# ControlBoardV3-4L.net
KiCad netlist of a schematic drawn in EAGLE
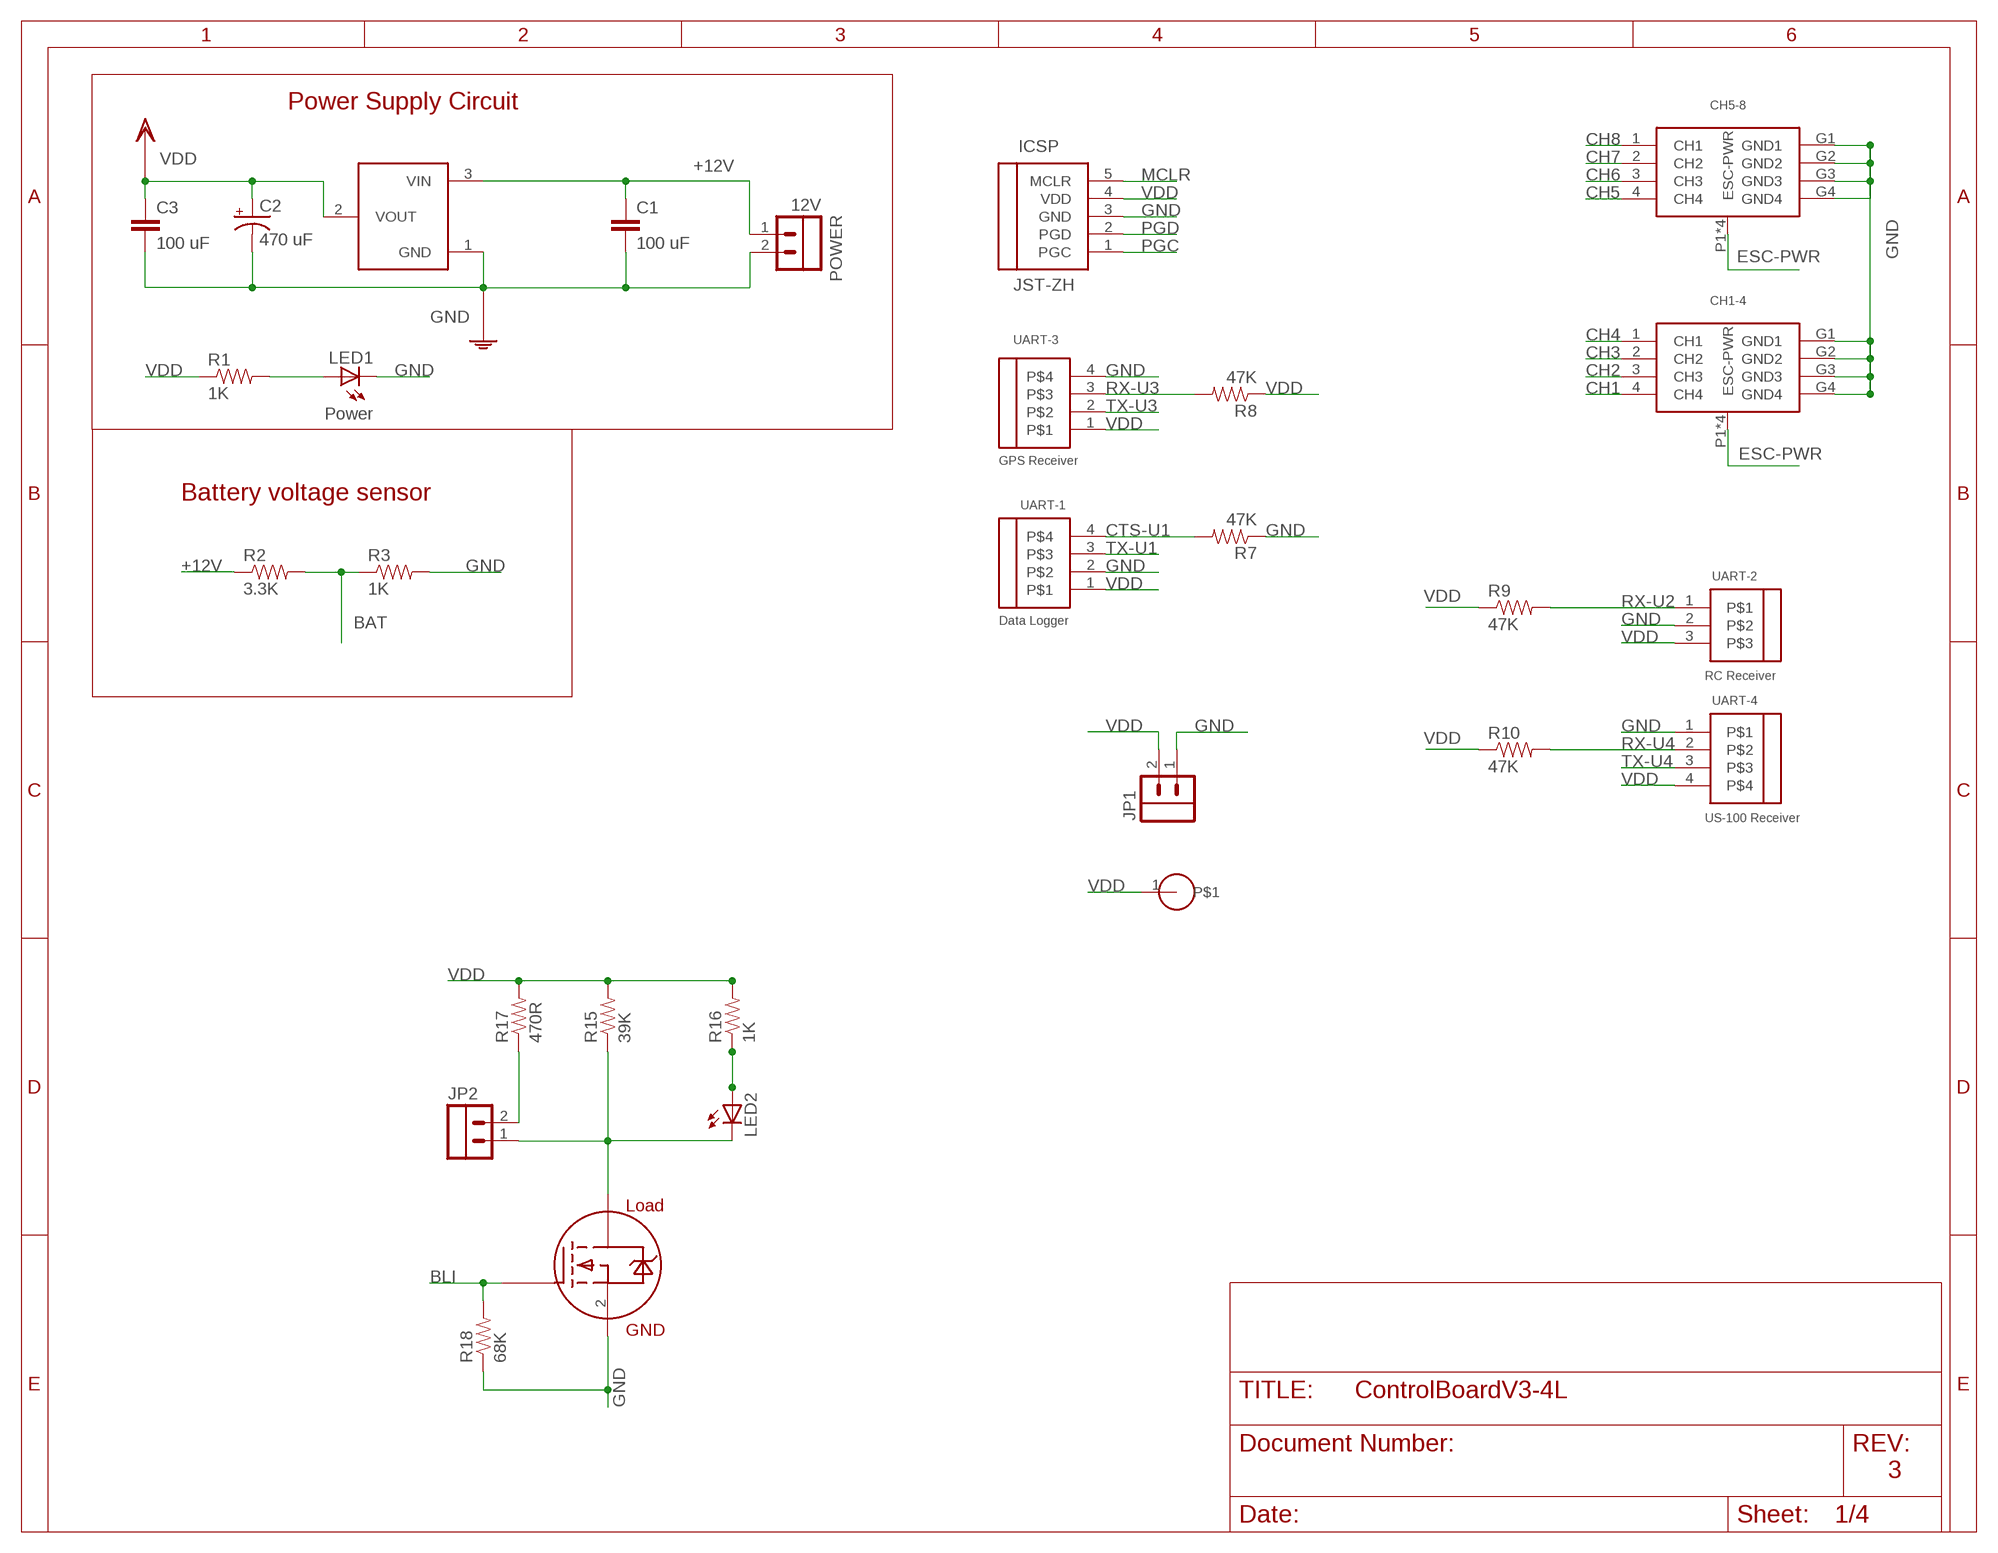
[diagram p0: schematic, sheet 1]
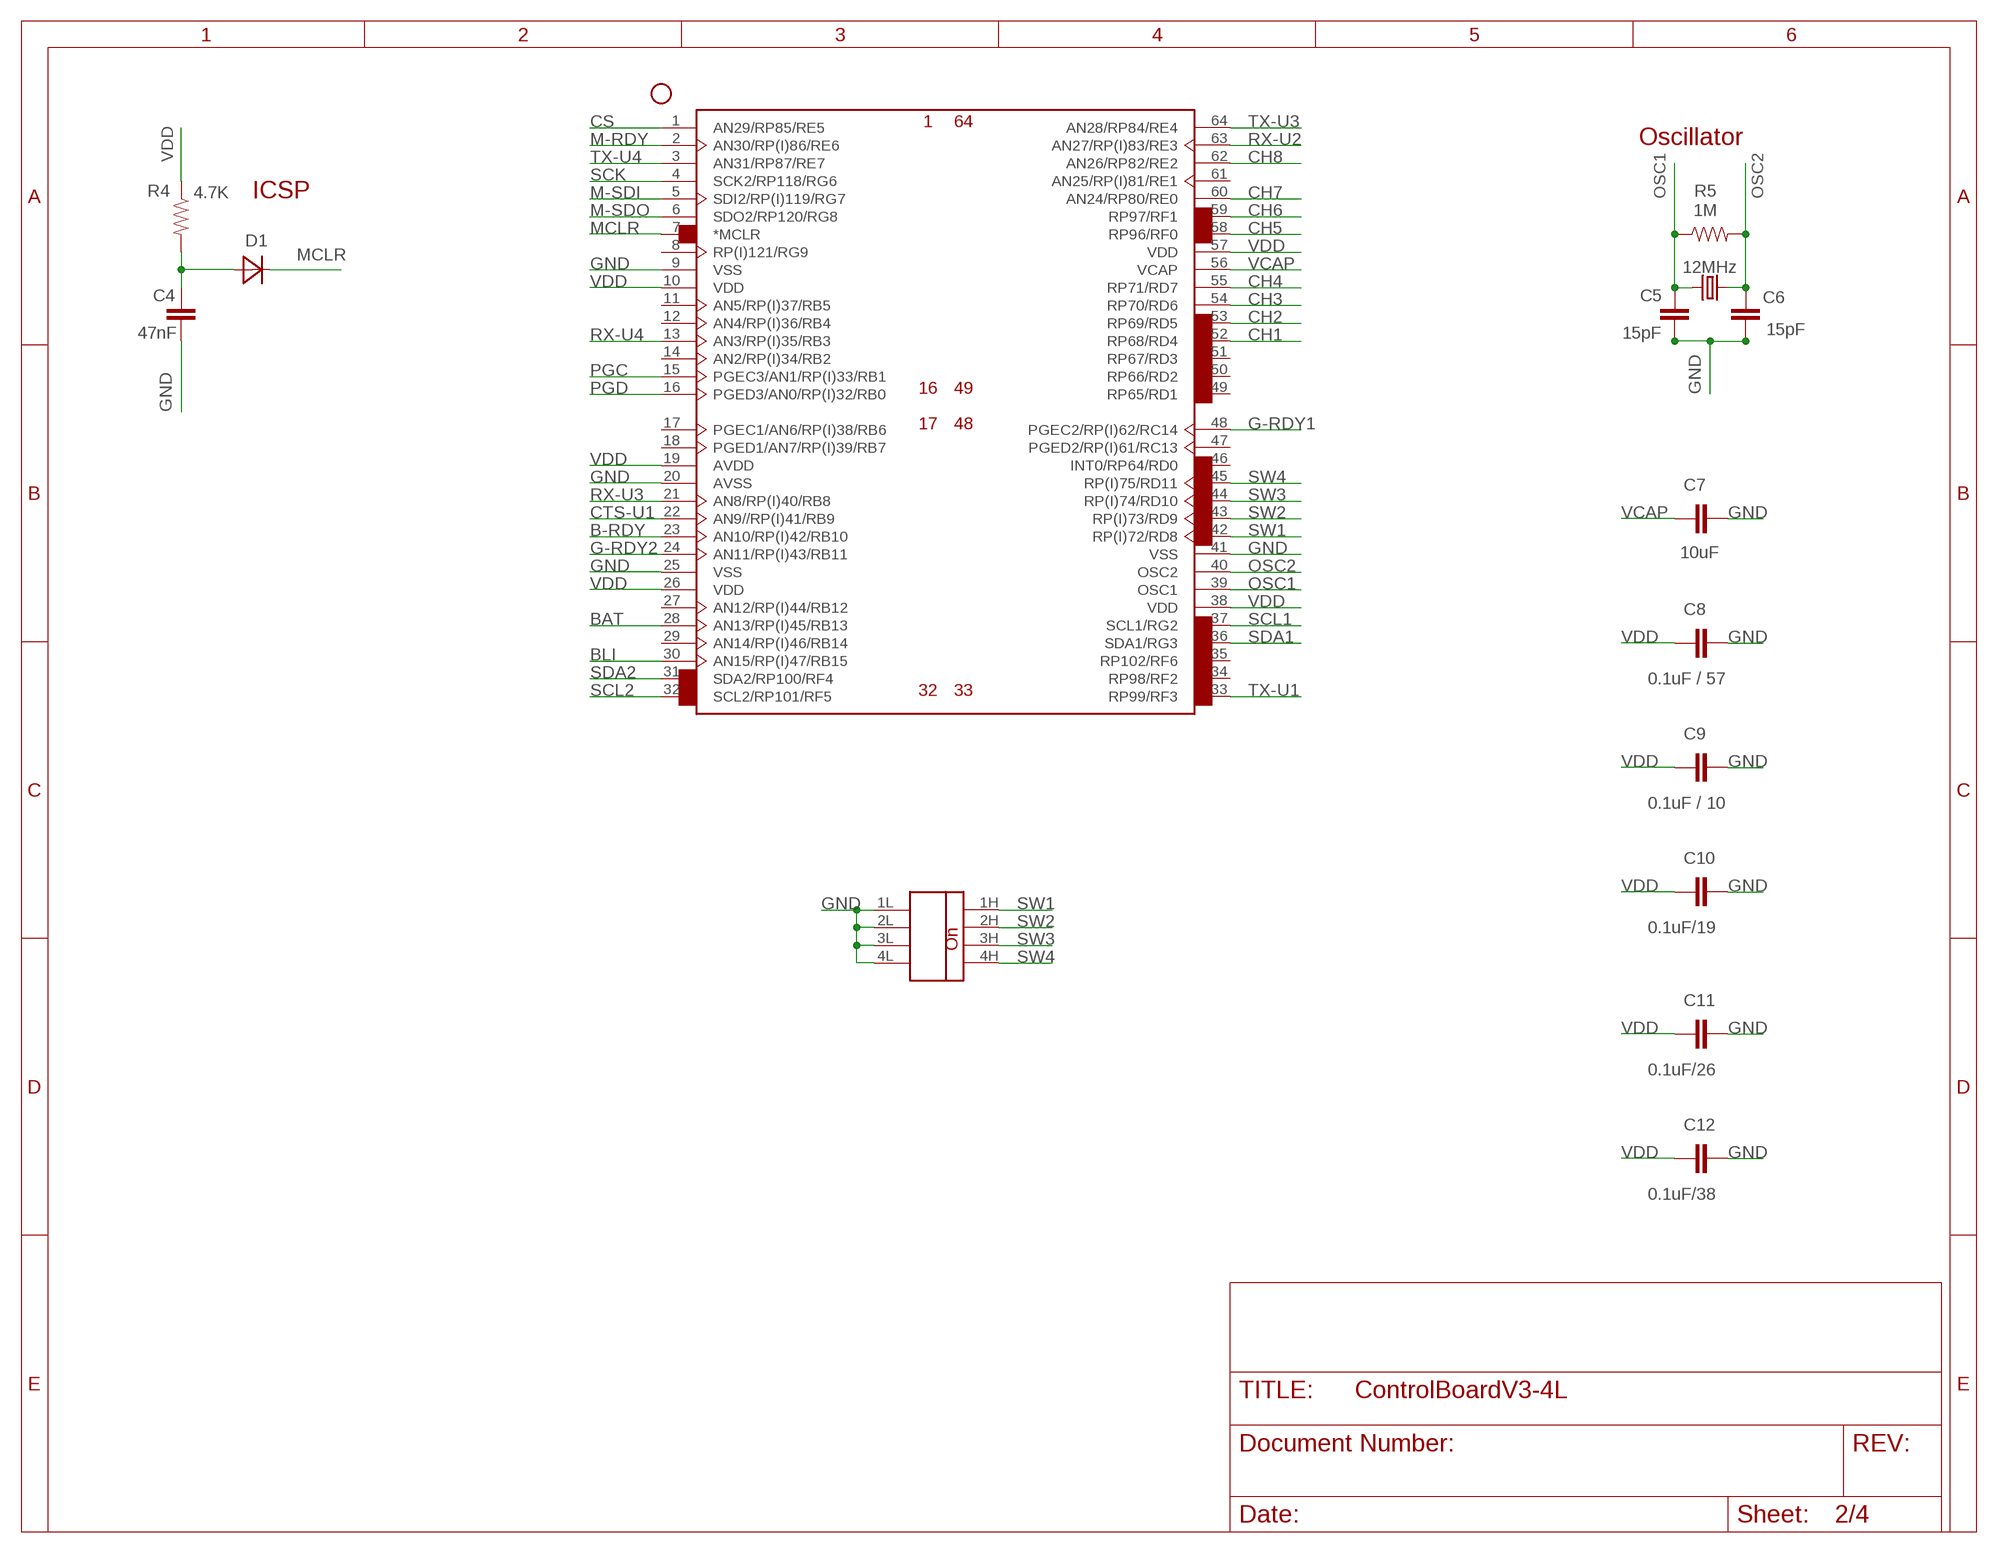
[diagram p1: schematic, sheet 2]
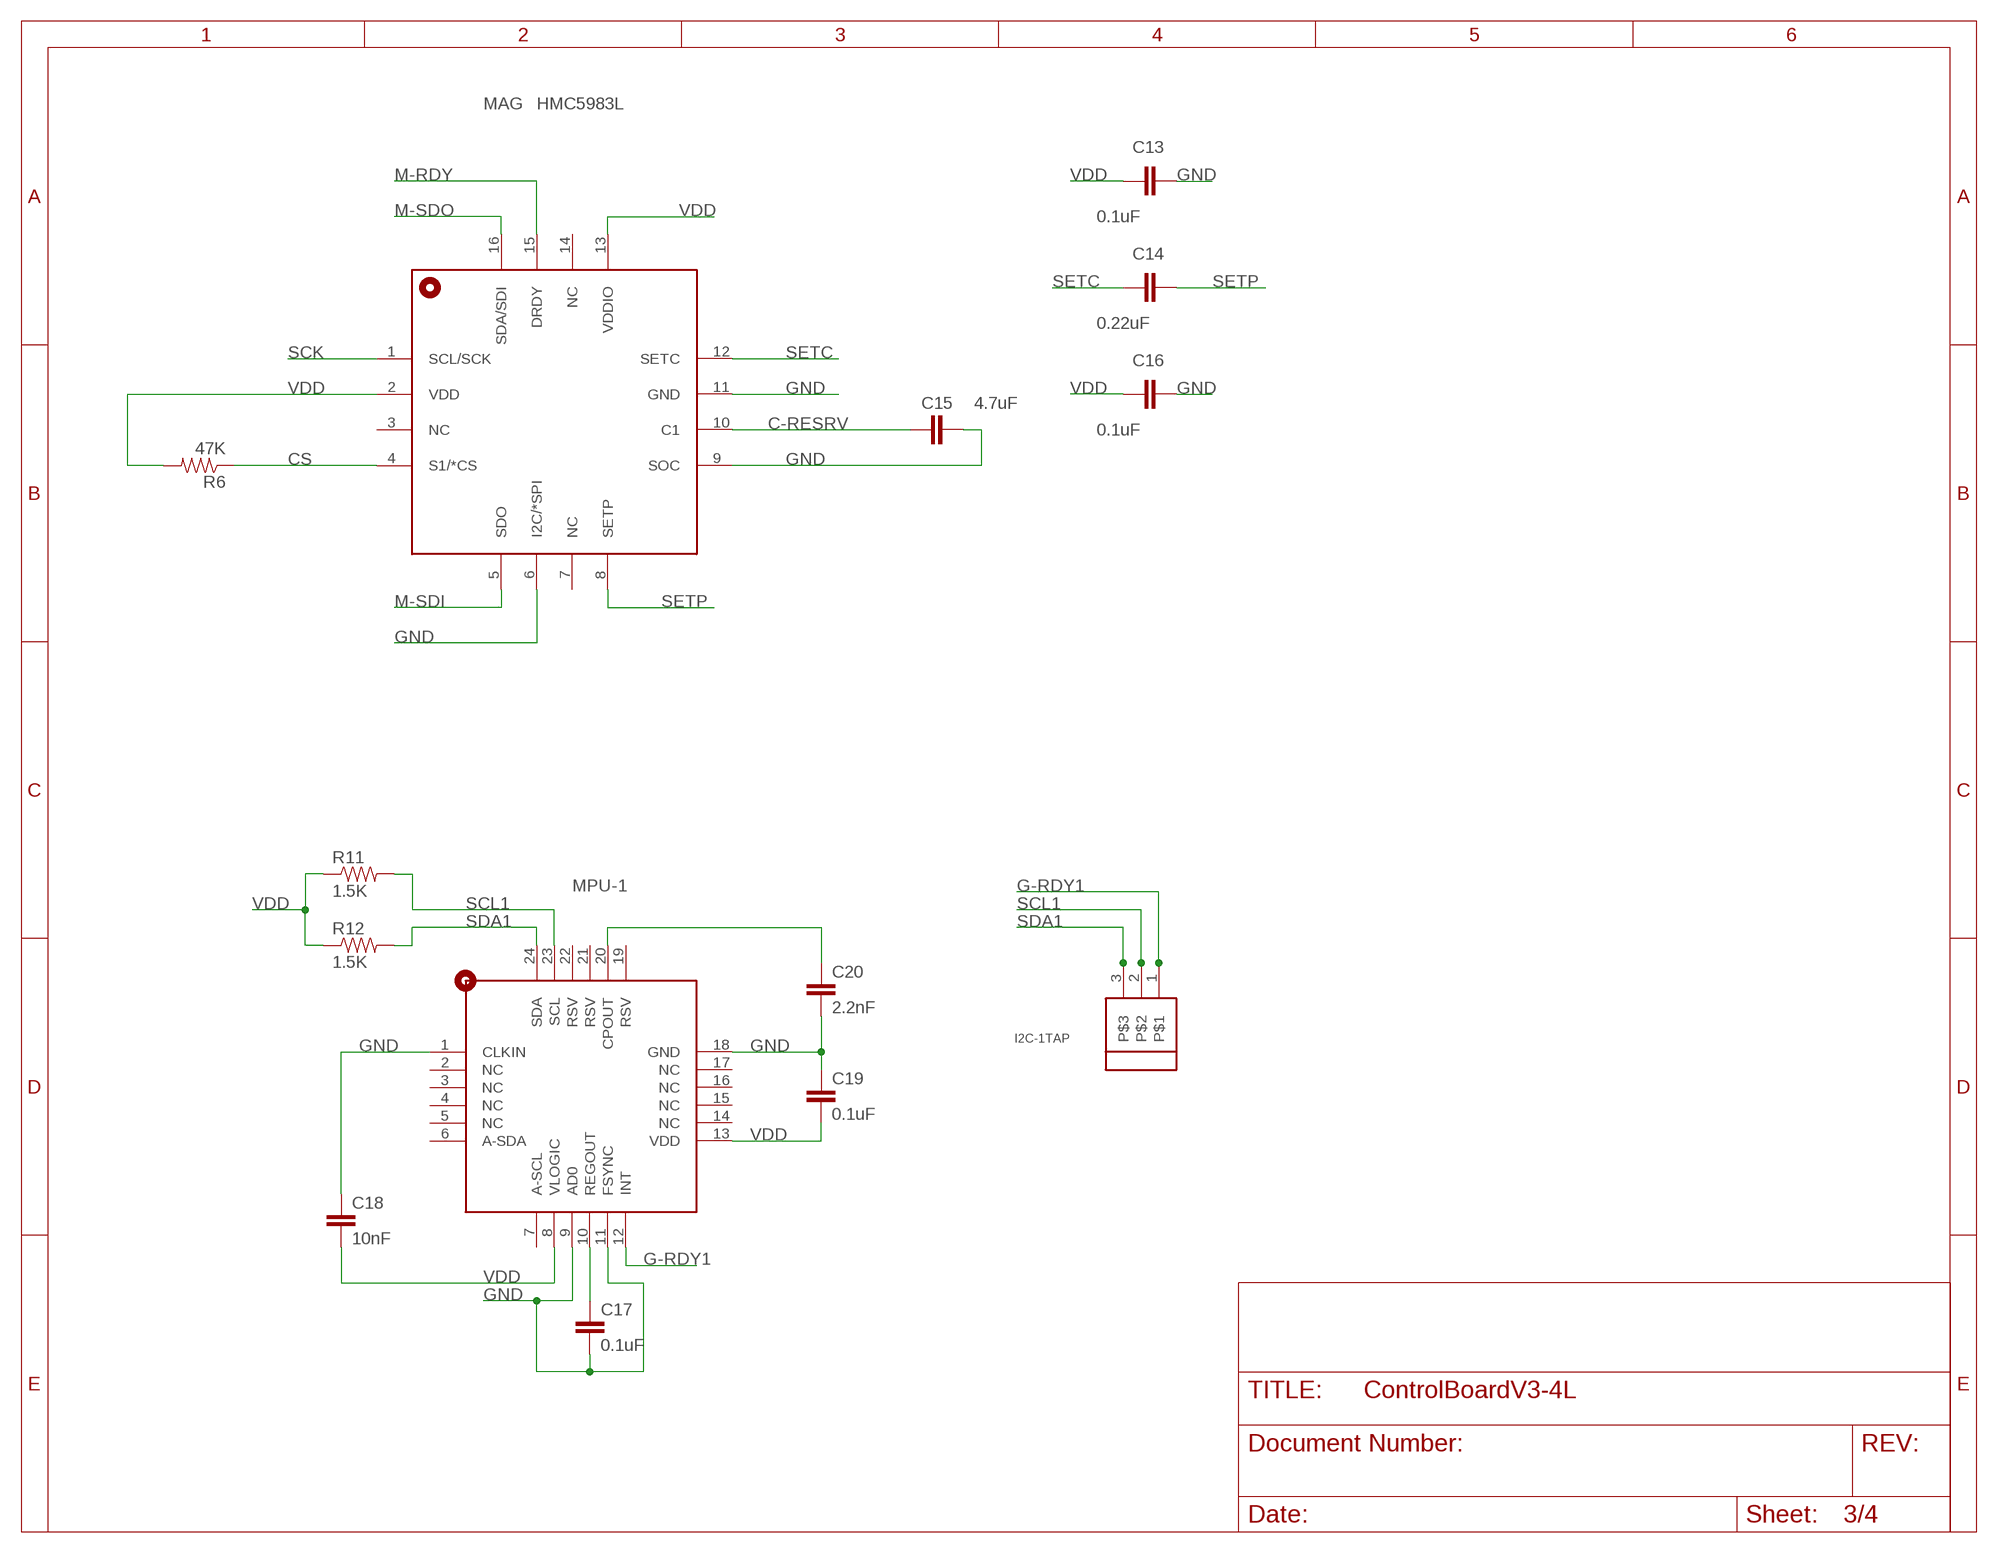
[diagram p2: schematic, sheet 3]
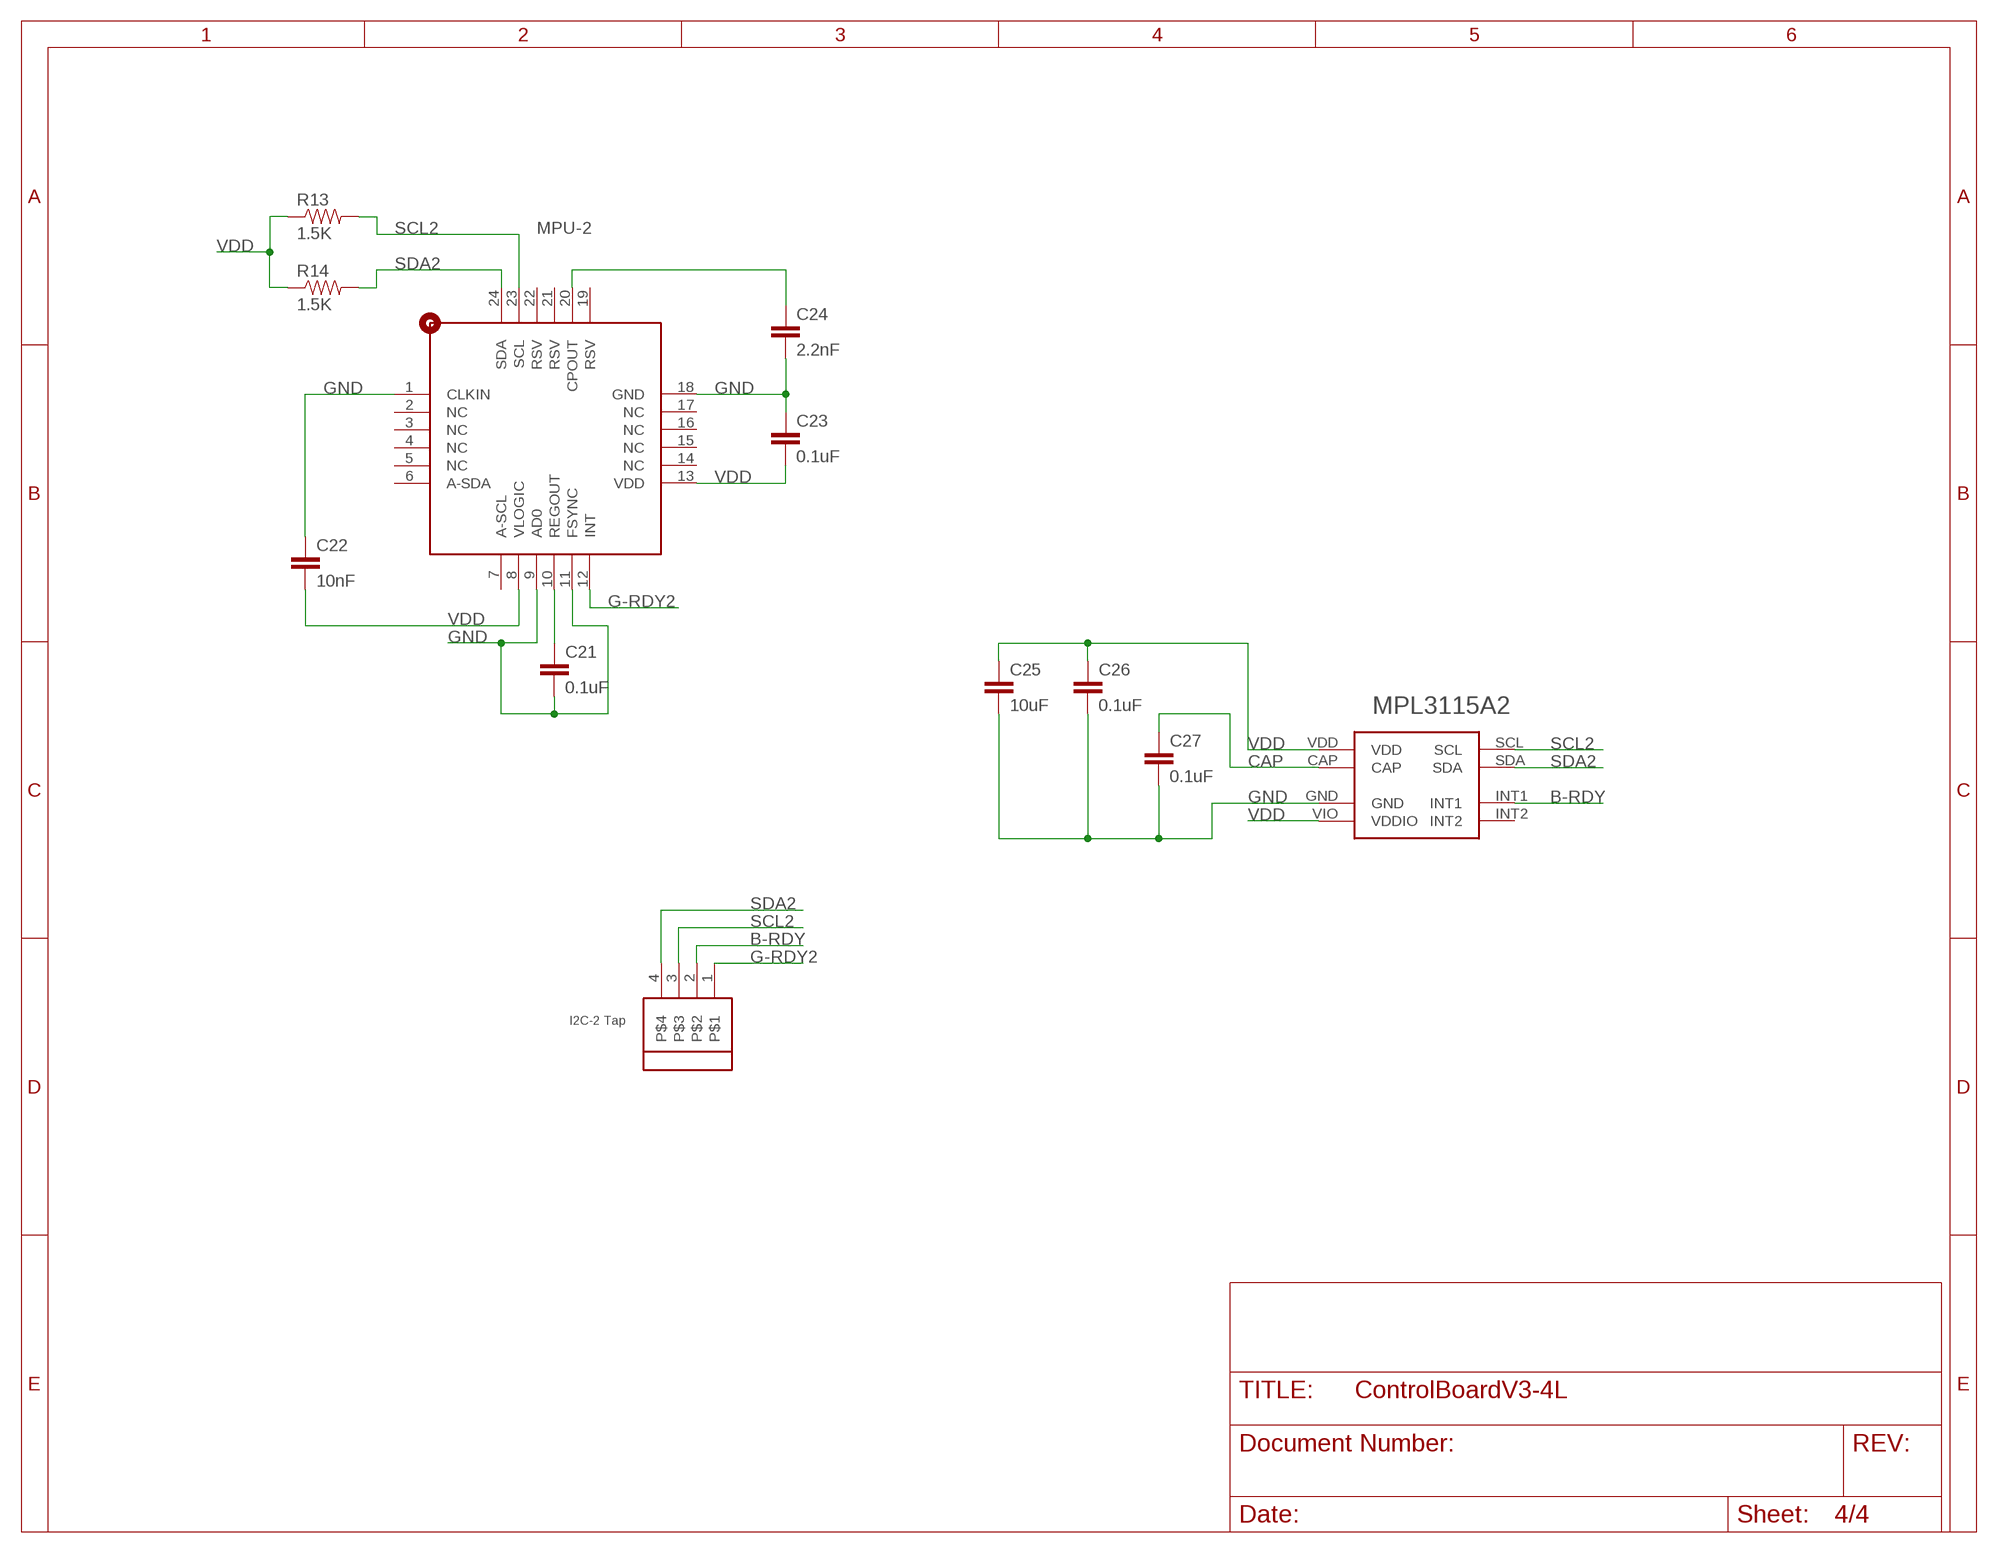
[diagram p3: schematic, sheet 4]

(export (version "E")
  (design (tool "Eeschema 10.0.6"))
  (components
    (comp (ref "C4")
      (value "47nF")
      (footprint "eagle-import:0805_INCH-HS-CAP")
      (libsource (lib "eagle-import") (part "CAP-CERAMIC_0805"))
    )
    (comp (ref "C5")
      (value "15pF")
      (footprint "eagle-import:0805_INCH-HS-CAP")
      (libsource (lib "eagle-import") (part "CAP-CERAMIC_0805"))
    )
    (comp (ref "C6")
      (value "15pF")
      (footprint "eagle-import:0805_INCH-HS-CAP")
      (libsource (lib "eagle-import") (part "CAP-CERAMIC_0805"))
    )
    (comp (ref "C7")
      (value "10uF")
      (footprint "eagle-import:1210_INCH-HS-CAP")
      (libsource (lib "eagle-import") (part "CAP-CERAMIC_1210"))
    )
    (comp (ref "C8")
      (value "0.1uF / 57")
      (footprint "eagle-import:0603_INCH-HS-CAP")
      (libsource (lib "eagle-import") (part "CAP-CERAMIC_0603"))
    )
    (comp (ref "C9")
      (value "0.1uF / 10")
      (footprint "eagle-import:0603_INCH-HS-CAP")
      (libsource (lib "eagle-import") (part "CAP-CERAMIC_0603"))
    )
    (comp (ref "C10")
      (value "0.1uF/19")
      (footprint "eagle-import:0603_INCH-HS-CAP")
      (libsource (lib "eagle-import") (part "CAP-CERAMIC_0603"))
    )
    (comp (ref "C11")
      (value "0.1uF/26")
      (footprint "eagle-import:0603_INCH-HS-CAP")
      (libsource (lib "eagle-import") (part "CAP-CERAMIC_0603"))
    )
    (comp (ref "C12")
      (value "0.1uF/38")
      (footprint "eagle-import:0603_INCH-HS-CAP")
      (libsource (lib "eagle-import") (part "CAP-CERAMIC_0603"))
    )
    (comp (ref "D1")
      (value "DIODE_1206")
      (footprint "eagle-import:1206_INCH-HS-DIODE")
      (libsource (lib "eagle-import") (part "DIODE_1206"))
    )
    (comp (ref "Q1")
      (value "12MHz")
      (footprint "eagle-import:CRYSTAL-SMD-5.0X3.2")
      (libsource (lib "eagle-import") (part "CRYSTAL_SMD-5.0X3.2"))
    )
    (comp (ref "R4")
      (value "4.7K")
      (footprint "eagle-import:0805_INCH-HS")
      (libsource (lib "eagle-import") (part "RESISTOR_0805"))
    )
    (comp (ref "R5")
      (value "1M")
      (footprint "eagle-import:0805_INCH-HS")
      (libsource (lib "eagle-import") (part "RESISTOR_0805"))
    )
    (comp (ref "U$1")
      (value "PIC24EP512GP806_TQFP64-10X10")
      (footprint "eagle-import:TQFP64-10X10X1MM")
      (libsource (lib "eagle-import") (part "PIC24EP512GP806_TQFP64-10X10"))
    )
    (comp (ref "U$3")
      (value "SWITCH-4_HALF-PITCH")
      (footprint "eagle-import:DIP-4-HP")
      (libsource (lib "eagle-import") (part "SWITCH-4_HALF-PITCH"))
    )
    (comp (ref "C21")
      (value "0.1uF")
      (footprint "eagle-import:0603_INCH-HS-CAP")
      (libsource (lib "eagle-import") (part "CAP-CERAMIC_0603"))
    )
    (comp (ref "C22")
      (value "10nF")
      (footprint "eagle-import:0603_INCH-HS-CAP")
      (libsource (lib "eagle-import") (part "CAP-CERAMIC_0603"))
    )
    (comp (ref "C23")
      (value "0.1uF")
      (footprint "eagle-import:0603_INCH-HS-CAP")
      (libsource (lib "eagle-import") (part "CAP-CERAMIC_0603"))
    )
    (comp (ref "C24")
      (value "2.2nF")
      (footprint "eagle-import:0805_INCH-HS-CAP")
      (libsource (lib "eagle-import") (part "CAP-CERAMIC_0805"))
    )
    (comp (ref "C25")
      (value "10uF")
      (footprint "eagle-import:1210_INCH-HS-CAP")
      (libsource (lib "eagle-import") (part "CAP-CERAMIC_1210"))
    )
    (comp (ref "C26")
      (value "0.1uF")
      (footprint "eagle-import:0603_INCH-HS-CAP")
      (libsource (lib "eagle-import") (part "CAP-CERAMIC_0603"))
    )
    (comp (ref "C27")
      (value "0.1uF")
      (footprint "eagle-import:0603_INCH-HS-CAP")
      (libsource (lib "eagle-import") (part "CAP-CERAMIC_0603"))
    )
    (comp (ref "MPL3115A2")
      (value "MPL-3115A2")
      (footprint "eagle-import:MPL-3115A2")
      (libsource (lib "eagle-import") (part "MPL-3115A2"))
    )
    (comp (ref "MPU-2")
      (value "MPU-6050-1")
      (footprint "eagle-import:MPU-6050_QFN-24-4MM2_AZ")
      (libsource (lib "eagle-import") (part "MPU-6050-1"))
    )
    (comp (ref "R13")
      (value "1.5K")
      (footprint "eagle-import:0805_INCH-HS")
      (libsource (lib "eagle-import") (part "RESISTOR_0805"))
    )
    (comp (ref "R14")
      (value "1.5K")
      (footprint "eagle-import:0805_INCH-HS")
      (libsource (lib "eagle-import") (part "RESISTOR_0805"))
    )
    (comp (ref "U$4")
      (value "I2C-2 Tap")
      (footprint "eagle-import:1X04-100MIL-MACHINED")
      (libsource (lib "eagle-import") (part "HEADER-04_MACHINED"))
    )
    (comp (ref "C1")
      (value "100 uF")
      (footprint "eagle-import:1210_INCH-HS-CAP")
      (libsource (lib "eagle-import") (part "CAP-CERAMIC_1210"))
    )
    (comp (ref "C2")
      (value "470 uF")
      (footprint "eagle-import:TANT-D-7343")
      (libsource (lib "eagle-import") (part "CAP-SMD-TANT_D-7343"))
    )
    (comp (ref "C3")
      (value "100 uF")
      (footprint "eagle-import:1210_INCH-HS-CAP")
      (libsource (lib "eagle-import") (part "CAP-CERAMIC_1210"))
    )
    (comp (ref "CH1-4")
      (value "4CH-PWM-PPM-HEADER")
      (footprint "eagle-import:4CH-PWM-PPM-HEADER-PACKAGE")
      (libsource (lib "eagle-import") (part "4CH-PWM-PPM-HEADER"))
    )
    (comp (ref "CH5-8")
      (value "4CH-PWM-PPM-HEADER")
      (footprint "eagle-import:4CH-PWM-PPM-HEADER-PACKAGE")
      (libsource (lib "eagle-import") (part "4CH-PWM-PPM-HEADER"))
    )
    (comp (ref "ICSP")
      (value "JST-ZH")
      (footprint "eagle-import:1X05-JST-ZH")
      (libsource (lib "eagle-import") (part "ICSP_JST-ZH"))
    )
    (comp (ref "JP1")
      (value "HEADER-02_JST_ZH")
      (footprint "eagle-import:1X02-JST-ZH")
      (libsource (lib "eagle-import") (part "HEADER-02_JST_ZH"))
    )
    (comp (ref "JP2")
      (value "HEADER-02_0.1\"_NO_SILK")
      (footprint "eagle-import:1X02_100MIL_NO_SILK")
      (libsource (lib "eagle-import") (part "HEADER-02_0.1{dblquote}_NO_SILK"))
    )
    (comp (ref "LED1")
      (value "Power")
      (footprint "eagle-import:1206_INCH-HS-LED")
      (libsource (lib "eagle-import") (part "LED_SMD_1206"))
    )
    (comp (ref "LED2")
      (value "LED_SMD_1206")
      (footprint "eagle-import:1206_INCH-HS-LED")
      (libsource (lib "eagle-import") (part "LED_SMD_1206"))
    )
    (comp (ref "POWER")
      (value "12V")
      (footprint "eagle-import:1X02_100MIL_LONGPADS")
      (libsource (lib "eagle-import") (part "HEADER-02_0.1{dblquote}_LONGPADS"))
    )
    (comp (ref "R1")
      (value "1K")
      (footprint "eagle-import:0805_INCH-HS")
      (libsource (lib "eagle-import") (part "RESISTOR_0805"))
    )
    (comp (ref "R2")
      (value "3.3K")
      (footprint "eagle-import:0805_INCH-HS")
      (libsource (lib "eagle-import") (part "RESISTOR_0805"))
    )
    (comp (ref "R3")
      (value "1K")
      (footprint "eagle-import:0805_INCH-HS")
      (libsource (lib "eagle-import") (part "RESISTOR_0805"))
    )
    (comp (ref "R7")
      (value "47K")
      (footprint "eagle-import:0805_INCH-HS")
      (libsource (lib "eagle-import") (part "RESISTOR_0805"))
    )
    (comp (ref "R8")
      (value "47K")
      (footprint "eagle-import:0805_INCH-HS")
      (libsource (lib "eagle-import") (part "RESISTOR_0805"))
    )
    (comp (ref "R9")
      (value "47K")
      (footprint "eagle-import:0805_INCH-HS")
      (libsource (lib "eagle-import") (part "RESISTOR_0805"))
    )
    (comp (ref "R10")
      (value "47K")
      (footprint "eagle-import:0805_INCH-HS")
      (libsource (lib "eagle-import") (part "RESISTOR_0805"))
    )
    (comp (ref "R15")
      (value "39K")
      (footprint "eagle-import:0805_INCH-HS")
      (libsource (lib "eagle-import") (part "RESISTOR_0805"))
    )
    (comp (ref "R16")
      (value "1K")
      (footprint "eagle-import:0805_INCH-HS")
      (libsource (lib "eagle-import") (part "RESISTOR_0805"))
    )
    (comp (ref "R17")
      (value "470R")
      (footprint "eagle-import:0805_INCH-HS")
      (libsource (lib "eagle-import") (part "RESISTOR_0805"))
    )
    (comp (ref "R18")
      (value "68K")
      (footprint "eagle-import:0805_INCH-HS")
      (libsource (lib "eagle-import") (part "RESISTOR_0805"))
    )
    (comp (ref "U$2")
      (value "NCP1117_DPAK")
      (footprint "eagle-import:DPAK-ONSEMI")
      (libsource (lib "eagle-import") (part "NCP1117_DPAK"))
    )
    (comp (ref "U$5")
      (value "N-MOSFET_SOT-323")
      (footprint "eagle-import:SOT-323")
      (libsource (lib "eagle-import") (part "N-MOSFET_SOT-323"))
    )
    (comp (ref "U$6")
      (value "TAP-01_PRECISE")
      (footprint "eagle-import:1X01_PRECISE")
      (libsource (lib "eagle-import") (part "TAP-01_PRECISE"))
    )
    (comp (ref "UART-1")
      (value "Data Logger")
      (footprint "eagle-import:1X04-JST-ZH")
      (libsource (lib "eagle-import") (part "HEADER-04_JST-ZH_JST-ZH"))
    )
    (comp (ref "UART-2")
      (value "RC Receiver")
      (footprint "eagle-import:1X03-JST-ZH")
      (libsource (lib "eagle-import") (part "HEADER-03_JST-ZH"))
    )
    (comp (ref "UART-3")
      (value "GPS Receiver")
      (footprint "eagle-import:1X04-MOLEX-PICOBLADE")
      (libsource (lib "eagle-import") (part "HEADER-04_MOLEX-1.25"))
    )
    (comp (ref "UART-4")
      (value "US-100 Receiver")
      (footprint "eagle-import:1X04-JST-ZH")
      (libsource (lib "eagle-import") (part "HEADER-04_JST-ZH_JST-ZH"))
    )
    (comp (ref "C13")
      (value "0.1uF")
      (footprint "eagle-import:0603_INCH-HS-CAP")
      (libsource (lib "eagle-import") (part "CAP-CERAMIC_0603"))
    )
    (comp (ref "C14")
      (value "0.22uF")
      (footprint "eagle-import:0603_INCH-HS-CAP")
      (libsource (lib "eagle-import") (part "CAP-CERAMIC_0603"))
    )
    (comp (ref "C15")
      (value "4.7uF")
      (footprint "eagle-import:0805_INCH-HS-CAP")
      (libsource (lib "eagle-import") (part "CAP-CERAMIC_0805"))
    )
    (comp (ref "C16")
      (value "0.1uF")
      (footprint "eagle-import:0603_INCH-HS-CAP")
      (libsource (lib "eagle-import") (part "CAP-CERAMIC_0603"))
    )
    (comp (ref "C17")
      (value "0.1uF")
      (footprint "eagle-import:0603_INCH-HS-CAP")
      (libsource (lib "eagle-import") (part "CAP-CERAMIC_0603"))
    )
    (comp (ref "C18")
      (value "10nF")
      (footprint "eagle-import:0603_INCH-HS-CAP")
      (libsource (lib "eagle-import") (part "CAP-CERAMIC_0603"))
    )
    (comp (ref "C19")
      (value "0.1uF")
      (footprint "eagle-import:0603_INCH-HS-CAP")
      (libsource (lib "eagle-import") (part "CAP-CERAMIC_0603"))
    )
    (comp (ref "C20")
      (value "2.2nF")
      (footprint "eagle-import:0805_INCH-HS-CAP")
      (libsource (lib "eagle-import") (part "CAP-CERAMIC_0805"))
    )
    (comp (ref "I2C-1TAP")
      (value "HEADER-03_MACHINED")
      (footprint "eagle-import:1X03-100MIL-MACHINED")
      (libsource (lib "eagle-import") (part "HEADER-03_MACHINED"))
    )
    (comp (ref "MAG")
      (value "HMC5983L")
      (footprint "eagle-import:HMC5X83L-16LPCC")
      (libsource (lib "eagle-import") (part "HMC5983L_16PLCC"))
    )
    (comp (ref "MPU-1")
      (value "MPU-6050-1")
      (footprint "eagle-import:MPU-6050_QFN-24-4MM2_AZ")
      (libsource (lib "eagle-import") (part "MPU-6050-1"))
    )
    (comp (ref "R6")
      (value "47K")
      (footprint "eagle-import:0805_INCH-HS")
      (libsource (lib "eagle-import") (part "RESISTOR_0805"))
    )
    (comp (ref "R11")
      (value "1.5K")
      (footprint "eagle-import:0805_INCH-HS")
      (libsource (lib "eagle-import") (part "RESISTOR_0805"))
    )
    (comp (ref "R12")
      (value "1.5K")
      (footprint "eagle-import:0805_INCH-HS")
      (libsource (lib "eagle-import") (part "RESISTOR_0805"))
    )
  )
  (nets
    (net (code "1") (name "+12V") (class "Default")
      (node (ref "C1") (pin "P$1") (pinfunction "1_P$1") (pintype "passive"))
      (node (ref "POWER") (pin "1") (pinfunction "1_1") (pintype "passive"))
      (node (ref "R2") (pin "1") (pinfunction "1_1") (pintype "passive"))
      (node (ref "U$2") (pin "3") (pinfunction "VIN_3") (pintype "bidirectional"))
    )
    (net (code "2") (name "B-RDY") (class "Default")
      (node (ref "MPL3115A2") (pin "INT1") (pinfunction "INT1_INT1") (pintype "bidirectional"))
      (node (ref "U$1") (pin "23") (pinfunction "AN10/RP(I)42/RB10_23") (pintype "passive"))
      (node (ref "U$4") (pin "2") (pinfunction "P$2_2") (pintype "bidirectional"))
    )
    (net (code "3") (name "BAT") (class "Default")
      (node (ref "R2") (pin "2") (pinfunction "2_2") (pintype "passive"))
      (node (ref "R3") (pin "1") (pinfunction "1_1") (pintype "passive"))
      (node (ref "U$1") (pin "28") (pinfunction "AN13/RP(I)45/RB13_28") (pintype "passive"))
    )
    (net (code "4") (name "BLI") (class "Default")
      (node (ref "R18") (pin "2") (pinfunction "2_2") (pintype "passive"))
      (node (ref "U$1") (pin "30") (pinfunction "AN15/RP(I)47/RB15_30") (pintype "passive"))
      (node (ref "U$5") (pin "1") (pinfunction "G_1") (pintype "input"))
    )
    (net (code "5") (name "C-RESRV") (class "Default")
      (node (ref "C15") (pin "1") (pinfunction "1_1") (pintype "passive"))
      (node (ref "MAG") (pin "10") (pinfunction "C1_10") (pintype "passive"))
    )
    (net (code "6") (name "CAP") (class "Default")
      (node (ref "C27") (pin "1") (pinfunction "1_1") (pintype "passive"))
      (node (ref "MPL3115A2") (pin "CAP") (pinfunction "CAP_CAP") (pintype "bidirectional"))
    )
    (net (code "7") (name "CH1") (class "Default")
      (node (ref "CH1-4") (pin "4") (pinfunction "CH4_4") (pintype "bidirectional"))
      (node (ref "U$1") (pin "52") (pinfunction "RP68/RD4_52") (pintype "bidirectional"))
    )
    (net (code "8") (name "CH2") (class "Default")
      (node (ref "CH1-4") (pin "3") (pinfunction "CH3_3") (pintype "bidirectional"))
      (node (ref "U$1") (pin "53") (pinfunction "RP69/RD5_53") (pintype "bidirectional"))
    )
    (net (code "9") (name "CH3") (class "Default")
      (node (ref "CH1-4") (pin "2") (pinfunction "CH2_2") (pintype "bidirectional"))
      (node (ref "U$1") (pin "54") (pinfunction "RP70/RD6_54") (pintype "bidirectional"))
    )
    (net (code "10") (name "CH4") (class "Default")
      (node (ref "CH1-4") (pin "1") (pinfunction "CH1_1") (pintype "bidirectional"))
      (node (ref "U$1") (pin "55") (pinfunction "RP71/RD7_55") (pintype "bidirectional"))
    )
    (net (code "11") (name "CH5") (class "Default")
      (node (ref "CH5-8") (pin "4") (pinfunction "CH4_4") (pintype "bidirectional"))
      (node (ref "U$1") (pin "58") (pinfunction "RP96/RF0_58") (pintype "bidirectional"))
    )
    (net (code "12") (name "CH6") (class "Default")
      (node (ref "CH5-8") (pin "3") (pinfunction "CH3_3") (pintype "bidirectional"))
      (node (ref "U$1") (pin "59") (pinfunction "RP97/RF1_59") (pintype "bidirectional"))
    )
    (net (code "13") (name "CH7") (class "Default")
      (node (ref "CH5-8") (pin "2") (pinfunction "CH2_2") (pintype "bidirectional"))
      (node (ref "U$1") (pin "60") (pinfunction "AN24/RP80/RE0_60") (pintype "bidirectional"))
    )
    (net (code "14") (name "CH8") (class "Default")
      (node (ref "CH5-8") (pin "1") (pinfunction "CH1_1") (pintype "bidirectional"))
      (node (ref "U$1") (pin "62") (pinfunction "AN26/RP82/RE2_62") (pintype "bidirectional"))
    )
    (net (code "15") (name "CS") (class "Default")
      (node (ref "MAG") (pin "4") (pinfunction "S1/*CS_4") (pintype "power_in"))
      (node (ref "R6") (pin "1") (pinfunction "1_1") (pintype "passive"))
      (node (ref "U$1") (pin "1") (pinfunction "AN29/RP85/RE5_1") (pintype "passive"))
    )
    (net (code "16") (name "CTS-U1") (class "Default")
      (node (ref "R7") (pin "2") (pinfunction "2_2") (pintype "passive"))
      (node (ref "U$1") (pin "22") (pinfunction "AN9//RP(I)41/RB9_22") (pintype "passive"))
      (node (ref "UART-1") (pin "4") (pinfunction "P$4_4") (pintype "bidirectional"))
    )
    (net (code "17") (name "ESC-PWR") (class "Default")
      (node (ref "CH1-4") (pin "P1") (pinfunction "ESC-PWR_P1") (pintype "power_in"))
      (node (ref "CH1-4") (pin "P2") (pinfunction "ESC-PWR_P2") (pintype "power_in"))
      (node (ref "CH1-4") (pin "P3") (pinfunction "ESC-PWR_P3") (pintype "power_in"))
      (node (ref "CH1-4") (pin "P4") (pinfunction "ESC-PWR_P4") (pintype "power_in"))
      (node (ref "CH5-8") (pin "P1") (pinfunction "ESC-PWR_P1") (pintype "power_in"))
      (node (ref "CH5-8") (pin "P2") (pinfunction "ESC-PWR_P2") (pintype "power_in"))
      (node (ref "CH5-8") (pin "P3") (pinfunction "ESC-PWR_P3") (pintype "power_in"))
      (node (ref "CH5-8") (pin "P4") (pinfunction "ESC-PWR_P4") (pintype "power_in"))
    )
    (net (code "18") (name "G-RDY1") (class "Default")
      (node (ref "I2C-1TAP") (pin "1") (pinfunction "P$1_1") (pintype "bidirectional"))
      (node (ref "MPU-1") (pin "12") (pinfunction "INT_12") (pintype "bidirectional"))
      (node (ref "U$1") (pin "48") (pinfunction "PGEC2/RP(I)62/RC14_48") (pintype "bidirectional"))
    )
    (net (code "19") (name "G-RDY2") (class "Default")
      (node (ref "MPU-2") (pin "12") (pinfunction "INT_12") (pintype "bidirectional"))
      (node (ref "U$1") (pin "24") (pinfunction "AN11/RP(I)43/RB11_24") (pintype "passive"))
      (node (ref "U$4") (pin "1") (pinfunction "P$1_1") (pintype "bidirectional"))
    )
    (net (code "20") (name "GND") (class "Default")
      (node (ref "C1") (pin "P$2") (pinfunction "2_P$2") (pintype "passive"))
      (node (ref "C10") (pin "2") (pinfunction "2_2") (pintype "passive"))
      (node (ref "C11") (pin "2") (pinfunction "2_2") (pintype "passive"))
      (node (ref "C12") (pin "2") (pinfunction "2_2") (pintype "passive"))
      (node (ref "C13") (pin "2") (pinfunction "2_2") (pintype "passive"))
      (node (ref "C15") (pin "2") (pinfunction "2_2") (pintype "passive"))
      (node (ref "C16") (pin "2") (pinfunction "2_2") (pintype "passive"))
      (node (ref "C17") (pin "2") (pinfunction "2_2") (pintype "passive"))
      (node (ref "C18") (pin "1") (pinfunction "1_1") (pintype "passive"))
      (node (ref "C19") (pin "1") (pinfunction "1_1") (pintype "passive"))
      (node (ref "C2") (pin "-") (pinfunction "-_-") (pintype "passive"))
      (node (ref "C20") (pin "2") (pinfunction "2_2") (pintype "passive"))
      (node (ref "C21") (pin "2") (pinfunction "2_2") (pintype "passive"))
      (node (ref "C22") (pin "1") (pinfunction "1_1") (pintype "passive"))
      (node (ref "C23") (pin "1") (pinfunction "1_1") (pintype "passive"))
      (node (ref "C24") (pin "2") (pinfunction "2_2") (pintype "passive"))
      (node (ref "C25") (pin "P$2") (pinfunction "2_P$2") (pintype "passive"))
      (node (ref "C26") (pin "2") (pinfunction "2_2") (pintype "passive"))
      (node (ref "C27") (pin "2") (pinfunction "2_2") (pintype "passive"))
      (node (ref "C3") (pin "P$2") (pinfunction "2_P$2") (pintype "passive"))
      (node (ref "C4") (pin "2") (pinfunction "2_2") (pintype "passive"))
      (node (ref "C5") (pin "1") (pinfunction "1_1") (pintype "passive"))
      (node (ref "C6") (pin "1") (pinfunction "1_1") (pintype "passive"))
      (node (ref "C7") (pin "P$2") (pinfunction "2_P$2") (pintype "passive"))
      (node (ref "C8") (pin "2") (pinfunction "2_2") (pintype "passive"))
      (node (ref "C9") (pin "2") (pinfunction "2_2") (pintype "passive"))
      (node (ref "CH1-4") (pin "G1") (pinfunction "GND1_G1") (pintype "power_in"))
      (node (ref "CH1-4") (pin "G2") (pinfunction "GND2_G2") (pintype "power_in"))
      (node (ref "CH1-4") (pin "G3") (pinfunction "GND3_G3") (pintype "power_in"))
      (node (ref "CH1-4") (pin "G4") (pinfunction "GND4_G4") (pintype "power_in"))
      (node (ref "CH5-8") (pin "G1") (pinfunction "GND1_G1") (pintype "power_in"))
      (node (ref "CH5-8") (pin "G2") (pinfunction "GND2_G2") (pintype "power_in"))
      (node (ref "CH5-8") (pin "G3") (pinfunction "GND3_G3") (pintype "power_in"))
      (node (ref "CH5-8") (pin "G4") (pinfunction "GND4_G4") (pintype "power_in"))
      (node (ref "ICSP") (pin "3") (pinfunction "GND_3") (pintype "bidirectional"))
      (node (ref "JP1") (pin "1") (pinfunction "1_1") (pintype "passive"))
      (node (ref "LED1") (pin "C") (pinfunction "C_C") (pintype "passive"))
      (node (ref "MAG") (pin "11") (pinfunction "GND_11") (pintype "power_in"))
      (node (ref "MAG") (pin "6") (pinfunction "I2C/*SPI_6") (pintype "bidirectional"))
      (node (ref "MAG") (pin "9") (pinfunction "SOC_9") (pintype "input"))
      (node (ref "MPL3115A2") (pin "GND") (pinfunction "GND_GND") (pintype "bidirectional"))
      (node (ref "MPU-1") (pin "1") (pinfunction "CLKIN_1") (pintype "bidirectional"))
      (node (ref "MPU-1") (pin "11") (pinfunction "FSYNC_11") (pintype "bidirectional"))
      (node (ref "MPU-1") (pin "18") (pinfunction "GND_18") (pintype "power_in"))
      (node (ref "MPU-1") (pin "9") (pinfunction "AD0_9") (pintype "bidirectional"))
      (node (ref "MPU-2") (pin "1") (pinfunction "CLKIN_1") (pintype "bidirectional"))
      (node (ref "MPU-2") (pin "11") (pinfunction "FSYNC_11") (pintype "bidirectional"))
      (node (ref "MPU-2") (pin "18") (pinfunction "GND_18") (pintype "power_in"))
      (node (ref "MPU-2") (pin "9") (pinfunction "AD0_9") (pintype "bidirectional"))
      (node (ref "POWER") (pin "2") (pinfunction "2_2") (pintype "passive"))
      (node (ref "R18") (pin "1") (pinfunction "1_1") (pintype "passive"))
      (node (ref "R3") (pin "2") (pinfunction "2_2") (pintype "passive"))
      (node (ref "R7") (pin "1") (pinfunction "1_1") (pintype "passive"))
      (node (ref "U$1") (pin "20") (pinfunction "AVSS_20") (pintype "power_in"))
      (node (ref "U$1") (pin "25") (pinfunction "VSS_25") (pintype "power_in"))
      (node (ref "U$1") (pin "41") (pinfunction "VSS_41") (pintype "bidirectional"))
      (node (ref "U$1") (pin "9") (pinfunction "VSS_9") (pintype "power_in"))
      (node (ref "U$2") (pin "1") (pinfunction "GND_1") (pintype "bidirectional"))
      (node (ref "U$3") (pin "1L") (pinfunction "1L_1L") (pintype "bidirectional"))
      (node (ref "U$3") (pin "2L") (pinfunction "2L_2L") (pintype "bidirectional"))
      (node (ref "U$3") (pin "3L") (pinfunction "3L_3L") (pintype "bidirectional"))
      (node (ref "U$3") (pin "4L") (pinfunction "4L_4L") (pintype "bidirectional"))
      (node (ref "U$5") (pin "2") (pinfunction "S_2") (pintype "bidirectional"))
      (node (ref "UART-1") (pin "2") (pinfunction "P$2_2") (pintype "bidirectional"))
      (node (ref "UART-2") (pin "2") (pinfunction "P$2_2") (pintype "bidirectional"))
      (node (ref "UART-3") (pin "4") (pinfunction "P$4_4") (pintype "bidirectional"))
      (node (ref "UART-4") (pin "1") (pinfunction "P$1_1") (pintype "bidirectional"))
    )
    (net (code "21") (name "M-RDY") (class "Default")
      (node (ref "MAG") (pin "15") (pinfunction "DRDY_15") (pintype "output"))
      (node (ref "U$1") (pin "2") (pinfunction "AN30/RP(I)86/RE6_2") (pintype "passive"))
    )
    (net (code "22") (name "M-SDI") (class "Default")
      (node (ref "MAG") (pin "5") (pinfunction "SDO_5") (pintype "bidirectional"))
      (node (ref "U$1") (pin "5") (pinfunction "SDI2/RP(I)119/RG7_5") (pintype "passive"))
    )
    (net (code "23") (name "M-SDO") (class "Default")
      (node (ref "MAG") (pin "16") (pinfunction "SDA/SDI_16") (pintype "bidirectional"))
      (node (ref "U$1") (pin "6") (pinfunction "SDO2/RP120/RG8_6") (pintype "passive"))
    )
    (net (code "24") (name "MCLR") (class "Default")
      (node (ref "D1") (pin "C") (pinfunction "C_C") (pintype "passive"))
      (node (ref "ICSP") (pin "5") (pinfunction "MCLR_5") (pintype "bidirectional"))
      (node (ref "U$1") (pin "7") (pinfunction "*MCLR_7") (pintype "passive"))
    )
    (net (code "25") (name "Net-(C4-Pad1)") (class "Default")
      (node (ref "C4") (pin "1") (pinfunction "1_1") (pintype "passive"))
      (node (ref "D1") (pin "A") (pinfunction "A_A") (pintype "passive"))
      (node (ref "R4") (pin "2") (pinfunction "2_2") (pintype "passive"))
    )
    (net (code "26") (name "Net-(JP2-Pad2)") (class "Default")
      (node (ref "JP2") (pin "2") (pinfunction "2_2") (pintype "passive"))
      (node (ref "R17") (pin "1") (pinfunction "1_1") (pintype "passive"))
    )
    (net (code "27") (name "Net-(LED1-PadA)") (class "Default")
      (node (ref "LED1") (pin "A") (pinfunction "A_A") (pintype "passive"))
      (node (ref "R1") (pin "2") (pinfunction "2_2") (pintype "passive"))
    )
    (net (code "28") (name "Net-(LED2-PadA)") (class "Default")
      (node (ref "LED2") (pin "A") (pinfunction "A_A") (pintype "passive"))
      (node (ref "R16") (pin "1") (pinfunction "1_1") (pintype "passive"))
    )
    (net (code "29") (name "Net-(MPU-1-CPOUT)") (class "Default")
      (node (ref "C20") (pin "1") (pinfunction "1_1") (pintype "passive"))
      (node (ref "MPU-1") (pin "20") (pinfunction "CPOUT_20") (pintype "bidirectional"))
    )
    (net (code "30") (name "Net-(MPU-1-REGOUT)") (class "Default")
      (node (ref "C17") (pin "1") (pinfunction "1_1") (pintype "passive"))
      (node (ref "MPU-1") (pin "10") (pinfunction "REGOUT_10") (pintype "bidirectional"))
    )
    (net (code "31") (name "Net-(MPU-2-CPOUT)") (class "Default")
      (node (ref "C24") (pin "1") (pinfunction "1_1") (pintype "passive"))
      (node (ref "MPU-2") (pin "20") (pinfunction "CPOUT_20") (pintype "bidirectional"))
    )
    (net (code "32") (name "Net-(MPU-2-REGOUT)") (class "Default")
      (node (ref "C21") (pin "1") (pinfunction "1_1") (pintype "passive"))
      (node (ref "MPU-2") (pin "10") (pinfunction "REGOUT_10") (pintype "bidirectional"))
    )
    (net (code "33") (name "Net-(U$5-D)") (class "Default")
      (node (ref "JP2") (pin "1") (pinfunction "1_1") (pintype "passive"))
      (node (ref "LED2") (pin "C") (pinfunction "C_C") (pintype "passive"))
      (node (ref "R15") (pin "1") (pinfunction "1_1") (pintype "passive"))
      (node (ref "U$5") (pin "3") (pinfunction "D_3") (pintype "bidirectional"))
    )
    (net (code "34") (name "OSC1") (class "Default")
      (node (ref "C5") (pin "2") (pinfunction "2_2") (pintype "passive"))
      (node (ref "Q1") (pin "P$2") (pinfunction "2_P$2") (pintype "passive"))
      (node (ref "R5") (pin "1") (pinfunction "1_1") (pintype "passive"))
      (node (ref "U$1") (pin "39") (pinfunction "OSC1_39") (pintype "bidirectional"))
    )
    (net (code "35") (name "OSC2") (class "Default")
      (node (ref "C6") (pin "2") (pinfunction "2_2") (pintype "passive"))
      (node (ref "Q1") (pin "P$1") (pinfunction "1_P$1") (pintype "passive"))
      (node (ref "R5") (pin "2") (pinfunction "2_2") (pintype "passive"))
      (node (ref "U$1") (pin "40") (pinfunction "OSC2_40") (pintype "bidirectional"))
    )
    (net (code "36") (name "PGC") (class "Default")
      (node (ref "ICSP") (pin "1") (pinfunction "PGC_1") (pintype "bidirectional"))
      (node (ref "U$1") (pin "15") (pinfunction "PGEC3/AN1/RP(I)33/RB1_15") (pintype "passive"))
    )
    (net (code "37") (name "PGD") (class "Default")
      (node (ref "ICSP") (pin "2") (pinfunction "PGD_2") (pintype "bidirectional"))
      (node (ref "U$1") (pin "16") (pinfunction "PGED3/AN0/RP(I)32/RB0_16") (pintype "passive"))
    )
    (net (code "38") (name "RX-U2") (class "Default")
      (node (ref "R9") (pin "2") (pinfunction "2_2") (pintype "passive"))
      (node (ref "U$1") (pin "63") (pinfunction "AN27/RP(I)83/RE3_63") (pintype "bidirectional"))
      (node (ref "UART-2") (pin "1") (pinfunction "P$1_1") (pintype "bidirectional"))
    )
    (net (code "39") (name "RX-U3") (class "Default")
      (node (ref "R8") (pin "2") (pinfunction "2_2") (pintype "passive"))
      (node (ref "U$1") (pin "21") (pinfunction "AN8/RP(I)40/RB8_21") (pintype "passive"))
      (node (ref "UART-3") (pin "3") (pinfunction "P$3_3") (pintype "bidirectional"))
    )
    (net (code "40") (name "RX-U4") (class "Default")
      (node (ref "R10") (pin "2") (pinfunction "2_2") (pintype "passive"))
      (node (ref "U$1") (pin "13") (pinfunction "AN3/RP(I)35/RB3_13") (pintype "passive"))
      (node (ref "UART-4") (pin "2") (pinfunction "P$2_2") (pintype "bidirectional"))
    )
    (net (code "41") (name "SCK") (class "Default")
      (node (ref "MAG") (pin "1") (pinfunction "SCL/SCK_1") (pintype "bidirectional"))
      (node (ref "U$1") (pin "4") (pinfunction "SCK2/RP118/RG6_4") (pintype "passive"))
    )
    (net (code "42") (name "SCL1") (class "Default")
      (node (ref "I2C-1TAP") (pin "2") (pinfunction "P$2_2") (pintype "bidirectional"))
      (node (ref "MPU-1") (pin "23") (pinfunction "SCL_23") (pintype "bidirectional"))
      (node (ref "R11") (pin "2") (pinfunction "2_2") (pintype "passive"))
      (node (ref "U$1") (pin "37") (pinfunction "SCL1/RG2_37") (pintype "bidirectional"))
    )
    (net (code "43") (name "SCL2") (class "Default")
      (node (ref "MPL3115A2") (pin "SCL") (pinfunction "SCL_SCL") (pintype "bidirectional"))
      (node (ref "MPU-2") (pin "23") (pinfunction "SCL_23") (pintype "bidirectional"))
      (node (ref "R13") (pin "2") (pinfunction "2_2") (pintype "passive"))
      (node (ref "U$1") (pin "32") (pinfunction "SCL2/RP101/RF5_32") (pintype "bidirectional"))
      (node (ref "U$4") (pin "3") (pinfunction "P$3_3") (pintype "bidirectional"))
    )
    (net (code "44") (name "SDA1") (class "Default")
      (node (ref "I2C-1TAP") (pin "3") (pinfunction "P$3_3") (pintype "bidirectional"))
      (node (ref "MPU-1") (pin "24") (pinfunction "SDA_24") (pintype "bidirectional"))
      (node (ref "R12") (pin "2") (pinfunction "2_2") (pintype "passive"))
      (node (ref "U$1") (pin "36") (pinfunction "SDA1/RG3_36") (pintype "bidirectional"))
    )
    (net (code "45") (name "SDA2") (class "Default")
      (node (ref "MPL3115A2") (pin "SDA") (pinfunction "SDA_SDA") (pintype "bidirectional"))
      (node (ref "MPU-2") (pin "24") (pinfunction "SDA_24") (pintype "bidirectional"))
      (node (ref "R14") (pin "2") (pinfunction "2_2") (pintype "passive"))
      (node (ref "U$1") (pin "31") (pinfunction "SDA2/RP100/RF4_31") (pintype "bidirectional"))
      (node (ref "U$4") (pin "4") (pinfunction "P$4_4") (pintype "bidirectional"))
    )
    (net (code "46") (name "SETC") (class "Default")
      (node (ref "C14") (pin "1") (pinfunction "1_1") (pintype "passive"))
      (node (ref "MAG") (pin "12") (pinfunction "SETC_12") (pintype "passive"))
    )
    (net (code "47") (name "SETP") (class "Default")
      (node (ref "C14") (pin "2") (pinfunction "2_2") (pintype "passive"))
      (node (ref "MAG") (pin "8") (pinfunction "SETP_8") (pintype "passive"))
    )
    (net (code "48") (name "SW1") (class "Default")
      (node (ref "U$1") (pin "42") (pinfunction "RP(I)72/RD8_42") (pintype "bidirectional"))
      (node (ref "U$3") (pin "1H") (pinfunction "1H_1H") (pintype "bidirectional"))
    )
    (net (code "49") (name "SW2") (class "Default")
      (node (ref "U$1") (pin "43") (pinfunction "RP(I)73/RD9_43") (pintype "bidirectional"))
      (node (ref "U$3") (pin "2H") (pinfunction "2H_2H") (pintype "bidirectional"))
    )
    (net (code "50") (name "SW3") (class "Default")
      (node (ref "U$1") (pin "44") (pinfunction "RP(I)74/RD10_44") (pintype "bidirectional"))
      (node (ref "U$3") (pin "3H") (pinfunction "3H_3H") (pintype "bidirectional"))
    )
    (net (code "51") (name "SW4") (class "Default")
      (node (ref "U$1") (pin "45") (pinfunction "RP(I)75/RD11_45") (pintype "bidirectional"))
      (node (ref "U$3") (pin "4H") (pinfunction "4H_4H") (pintype "bidirectional"))
    )
    (net (code "52") (name "TX-U1") (class "Default")
      (node (ref "U$1") (pin "33") (pinfunction "RP99/RF3_33") (pintype "bidirectional"))
      (node (ref "UART-1") (pin "3") (pinfunction "P$3_3") (pintype "bidirectional"))
    )
    (net (code "53") (name "TX-U3") (class "Default")
      (node (ref "U$1") (pin "64") (pinfunction "AN28/RP84/RE4_64") (pintype "bidirectional"))
      (node (ref "UART-3") (pin "2") (pinfunction "P$2_2") (pintype "bidirectional"))
    )
    (net (code "54") (name "TX-U4") (class "Default")
      (node (ref "U$1") (pin "3") (pinfunction "AN31/RP87/RE7_3") (pintype "passive"))
      (node (ref "UART-4") (pin "3") (pinfunction "P$3_3") (pintype "bidirectional"))
    )
    (net (code "55") (name "VCAP") (class "Default")
      (node (ref "C7") (pin "P$1") (pinfunction "1_P$1") (pintype "passive"))
      (node (ref "U$1") (pin "56") (pinfunction "VCAP_56") (pintype "bidirectional"))
    )
    (net (code "56") (name "VDD") (class "Default")
      (node (ref "C10") (pin "1") (pinfunction "1_1") (pintype "passive"))
      (node (ref "C11") (pin "1") (pinfunction "1_1") (pintype "passive"))
      (node (ref "C12") (pin "1") (pinfunction "1_1") (pintype "passive"))
      (node (ref "C13") (pin "1") (pinfunction "1_1") (pintype "passive"))
      (node (ref "C16") (pin "1") (pinfunction "1_1") (pintype "passive"))
      (node (ref "C18") (pin "2") (pinfunction "2_2") (pintype "passive"))
      (node (ref "C19") (pin "2") (pinfunction "2_2") (pintype "passive"))
      (node (ref "C2") (pin "+") (pinfunction "+_+") (pintype "passive"))
      (node (ref "C22") (pin "2") (pinfunction "2_2") (pintype "passive"))
      (node (ref "C23") (pin "2") (pinfunction "2_2") (pintype "passive"))
      (node (ref "C25") (pin "P$1") (pinfunction "1_P$1") (pintype "passive"))
      (node (ref "C26") (pin "1") (pinfunction "1_1") (pintype "passive"))
      (node (ref "C3") (pin "P$1") (pinfunction "1_P$1") (pintype "passive"))
      (node (ref "C8") (pin "1") (pinfunction "1_1") (pintype "passive"))
      (node (ref "C9") (pin "1") (pinfunction "1_1") (pintype "passive"))
      (node (ref "ICSP") (pin "4") (pinfunction "VDD_4") (pintype "bidirectional"))
      (node (ref "JP1") (pin "2") (pinfunction "2_2") (pintype "passive"))
      (node (ref "MAG") (pin "13") (pinfunction "VDDIO_13") (pintype "power_in"))
      (node (ref "MAG") (pin "2") (pinfunction "VDD_2") (pintype "power_in"))
      (node (ref "MPL3115A2") (pin "VDD") (pinfunction "VDD_VDD") (pintype "bidirectional"))
      (node (ref "MPL3115A2") (pin "VIO") (pinfunction "VDDIO_VIO") (pintype "bidirectional"))
      (node (ref "MPU-1") (pin "13") (pinfunction "VDD_13") (pintype "power_in"))
      (node (ref "MPU-1") (pin "8") (pinfunction "VLOGIC_8") (pintype "bidirectional"))
      (node (ref "MPU-2") (pin "13") (pinfunction "VDD_13") (pintype "power_in"))
      (node (ref "MPU-2") (pin "8") (pinfunction "VLOGIC_8") (pintype "bidirectional"))
      (node (ref "R1") (pin "1") (pinfunction "1_1") (pintype "passive"))
      (node (ref "R10") (pin "1") (pinfunction "1_1") (pintype "passive"))
      (node (ref "R11") (pin "1") (pinfunction "1_1") (pintype "passive"))
      (node (ref "R12") (pin "1") (pinfunction "1_1") (pintype "passive"))
      (node (ref "R13") (pin "1") (pinfunction "1_1") (pintype "passive"))
      (node (ref "R14") (pin "1") (pinfunction "1_1") (pintype "passive"))
      (node (ref "R15") (pin "2") (pinfunction "2_2") (pintype "passive"))
      (node (ref "R16") (pin "2") (pinfunction "2_2") (pintype "passive"))
      (node (ref "R17") (pin "2") (pinfunction "2_2") (pintype "passive"))
      (node (ref "R4") (pin "1") (pinfunction "1_1") (pintype "passive"))
      (node (ref "R6") (pin "2") (pinfunction "2_2") (pintype "passive"))
      (node (ref "R8") (pin "1") (pinfunction "1_1") (pintype "passive"))
      (node (ref "R9") (pin "1") (pinfunction "1_1") (pintype "passive"))
      (node (ref "U$1") (pin "10") (pinfunction "VDD_10") (pintype "power_in"))
      (node (ref "U$1") (pin "19") (pinfunction "AVDD_19") (pintype "power_in"))
      (node (ref "U$1") (pin "26") (pinfunction "VDD_26") (pintype "power_in"))
      (node (ref "U$1") (pin "38") (pinfunction "VDD_38") (pintype "bidirectional"))
      (node (ref "U$1") (pin "57") (pinfunction "VDD_57") (pintype "bidirectional"))
      (node (ref "U$2") (pin "2") (pinfunction "VOUT_2") (pintype "bidirectional"))
      (node (ref "U$6") (pin "1") (pinfunction "P$1_1") (pintype "bidirectional"))
      (node (ref "UART-1") (pin "1") (pinfunction "P$1_1") (pintype "bidirectional"))
      (node (ref "UART-2") (pin "3") (pinfunction "P$3_3") (pintype "bidirectional"))
      (node (ref "UART-3") (pin "1") (pinfunction "P$1_1") (pintype "bidirectional"))
      (node (ref "UART-4") (pin "4") (pinfunction "P$4_4") (pintype "bidirectional"))
    )
    (net (code "57") (name "unconnected-(MAG-NC-Pad3)") (class "Default")
      (node (ref "MAG") (pin "3") (pinfunction "NC_3") (pintype "no_connect"))
    )
    (net (code "58") (name "unconnected-(MAG-NC-Pad7)") (class "Default")
      (node (ref "MAG") (pin "7") (pinfunction "NC_7") (pintype "no_connect"))
    )
    (net (code "59") (name "unconnected-(MAG-NC-Pad14)") (class "Default")
      (node (ref "MAG") (pin "14") (pinfunction "NC_14") (pintype "no_connect"))
    )
    (net (code "60") (name "unconnected-(MPL3115A2-PadINT2)") (class "Default")
      (node (ref "MPL3115A2") (pin "INT2") (pinfunction "INT2_INT2") (pintype "bidirectional"))
    )
    (net (code "61") (name "unconnected-(MPU-1-A-SCL-Pad7)") (class "Default")
      (node (ref "MPU-1") (pin "7") (pinfunction "A-SCL_7") (pintype "bidirectional"))
    )
    (net (code "62") (name "unconnected-(MPU-1-A-SDA-Pad6)") (class "Default")
      (node (ref "MPU-1") (pin "6") (pinfunction "A-SDA_6") (pintype "bidirectional"))
    )
    (net (code "63") (name "unconnected-(MPU-1-NC-Pad2)") (class "Default")
      (node (ref "MPU-1") (pin "2") (pinfunction "NC_2") (pintype "no_connect"))
    )
    (net (code "64") (name "unconnected-(MPU-1-NC-Pad3)") (class "Default")
      (node (ref "MPU-1") (pin "3") (pinfunction "NC_3") (pintype "no_connect"))
    )
    (net (code "65") (name "unconnected-(MPU-1-NC-Pad4)") (class "Default")
      (node (ref "MPU-1") (pin "4") (pinfunction "NC_4") (pintype "no_connect"))
    )
    (net (code "66") (name "unconnected-(MPU-1-NC-Pad5)") (class "Default")
      (node (ref "MPU-1") (pin "5") (pinfunction "NC_5") (pintype "no_connect"))
    )
    (net (code "67") (name "unconnected-(MPU-1-NC-Pad14)") (class "Default")
      (node (ref "MPU-1") (pin "14") (pinfunction "NC_14") (pintype "no_connect"))
    )
    (net (code "68") (name "unconnected-(MPU-1-NC-Pad15)") (class "Default")
      (node (ref "MPU-1") (pin "15") (pinfunction "NC_15") (pintype "no_connect"))
    )
    (net (code "69") (name "unconnected-(MPU-1-NC-Pad16)") (class "Default")
      (node (ref "MPU-1") (pin "16") (pinfunction "NC_16") (pintype "no_connect"))
    )
    (net (code "70") (name "unconnected-(MPU-1-NC-Pad17)") (class "Default")
      (node (ref "MPU-1") (pin "17") (pinfunction "NC_17") (pintype "no_connect"))
    )
    (net (code "71") (name "unconnected-(MPU-1-RSV-Pad19)") (class "Default")
      (node (ref "MPU-1") (pin "19") (pinfunction "RSV_19") (pintype "no_connect"))
    )
    (net (code "72") (name "unconnected-(MPU-1-RSV-Pad21)") (class "Default")
      (node (ref "MPU-1") (pin "21") (pinfunction "RSV_21") (pintype "no_connect"))
    )
    (net (code "73") (name "unconnected-(MPU-1-RSV-Pad22)") (class "Default")
      (node (ref "MPU-1") (pin "22") (pinfunction "RSV_22") (pintype "bidirectional"))
    )
    (net (code "74") (name "unconnected-(MPU-2-A-SCL-Pad7)") (class "Default")
      (node (ref "MPU-2") (pin "7") (pinfunction "A-SCL_7") (pintype "bidirectional"))
    )
    (net (code "75") (name "unconnected-(MPU-2-A-SDA-Pad6)") (class "Default")
      (node (ref "MPU-2") (pin "6") (pinfunction "A-SDA_6") (pintype "bidirectional"))
    )
    (net (code "76") (name "unconnected-(MPU-2-NC-Pad2)") (class "Default")
      (node (ref "MPU-2") (pin "2") (pinfunction "NC_2") (pintype "no_connect"))
    )
    (net (code "77") (name "unconnected-(MPU-2-NC-Pad3)") (class "Default")
      (node (ref "MPU-2") (pin "3") (pinfunction "NC_3") (pintype "no_connect"))
    )
    (net (code "78") (name "unconnected-(MPU-2-NC-Pad4)") (class "Default")
      (node (ref "MPU-2") (pin "4") (pinfunction "NC_4") (pintype "no_connect"))
    )
    (net (code "79") (name "unconnected-(MPU-2-NC-Pad5)") (class "Default")
      (node (ref "MPU-2") (pin "5") (pinfunction "NC_5") (pintype "no_connect"))
    )
    (net (code "80") (name "unconnected-(MPU-2-NC-Pad14)") (class "Default")
      (node (ref "MPU-2") (pin "14") (pinfunction "NC_14") (pintype "no_connect"))
    )
    (net (code "81") (name "unconnected-(MPU-2-NC-Pad15)") (class "Default")
      (node (ref "MPU-2") (pin "15") (pinfunction "NC_15") (pintype "no_connect"))
    )
    (net (code "82") (name "unconnected-(MPU-2-NC-Pad16)") (class "Default")
      (node (ref "MPU-2") (pin "16") (pinfunction "NC_16") (pintype "no_connect"))
    )
    (net (code "83") (name "unconnected-(MPU-2-NC-Pad17)") (class "Default")
      (node (ref "MPU-2") (pin "17") (pinfunction "NC_17") (pintype "no_connect"))
    )
    (net (code "84") (name "unconnected-(MPU-2-RSV-Pad19)") (class "Default")
      (node (ref "MPU-2") (pin "19") (pinfunction "RSV_19") (pintype "no_connect"))
    )
    (net (code "85") (name "unconnected-(MPU-2-RSV-Pad21)") (class "Default")
      (node (ref "MPU-2") (pin "21") (pinfunction "RSV_21") (pintype "no_connect"))
    )
    (net (code "86") (name "unconnected-(MPU-2-RSV-Pad22)") (class "Default")
      (node (ref "MPU-2") (pin "22") (pinfunction "RSV_22") (pintype "bidirectional"))
    )
    (net (code "87") (name "unconnected-(U$1-AN2{slash}RP(I)34{slash}RB2-Pad14)") (class "Default")
      (node (ref "U$1") (pin "14") (pinfunction "AN2/RP(I)34/RB2_14") (pintype "passive"))
    )
    (net (code "88") (name "unconnected-(U$1-AN4{slash}RP(I)36{slash}RB4-Pad12)") (class "Default")
      (node (ref "U$1") (pin "12") (pinfunction "AN4/RP(I)36/RB4_12") (pintype "passive"))
    )
    (net (code "89") (name "unconnected-(U$1-AN5{slash}RP(I)37{slash}RB5-Pad11)") (class "Default")
      (node (ref "U$1") (pin "11") (pinfunction "AN5/RP(I)37/RB5_11") (pintype "passive"))
    )
    (net (code "90") (name "unconnected-(U$1-AN12{slash}RP(I)44{slash}RB12-Pad27)") (class "Default")
      (node (ref "U$1") (pin "27") (pinfunction "AN12/RP(I)44/RB12_27") (pintype "passive"))
    )
    (net (code "91") (name "unconnected-(U$1-AN14{slash}RP(I)46{slash}RB14-Pad29)") (class "Default")
      (node (ref "U$1") (pin "29") (pinfunction "AN14/RP(I)46/RB14_29") (pintype "passive"))
    )
    (net (code "92") (name "unconnected-(U$1-AN25{slash}RP(I)81{slash}RE1-Pad61)") (class "Default")
      (node (ref "U$1") (pin "61") (pinfunction "AN25/RP(I)81/RE1_61") (pintype "bidirectional"))
    )
    (net (code "93") (name "unconnected-(U$1-INT0{slash}RP64{slash}RD0-Pad46)") (class "Default")
      (node (ref "U$1") (pin "46") (pinfunction "INT0/RP64/RD0_46") (pintype "bidirectional"))
    )
    (net (code "94") (name "unconnected-(U$1-PGEC1{slash}AN6{slash}RP(I)38{slash}RB6-Pad17)") (class "Default")
      (node (ref "U$1") (pin "17") (pinfunction "PGEC1/AN6/RP(I)38/RB6_17") (pintype "passive"))
    )
    (net (code "95") (name "unconnected-(U$1-PGED1{slash}AN7{slash}RP(I)39{slash}RB7-Pad18)") (class "Default")
      (node (ref "U$1") (pin "18") (pinfunction "PGED1/AN7/RP(I)39/RB7_18") (pintype "passive"))
    )
    (net (code "96") (name "unconnected-(U$1-PGED2{slash}RP(I)61{slash}RC13-Pad47)") (class "Default")
      (node (ref "U$1") (pin "47") (pinfunction "PGED2/RP(I)61/RC13_47") (pintype "bidirectional"))
    )
    (net (code "97") (name "unconnected-(U$1-RP(I)121{slash}RG9-Pad8)") (class "Default")
      (node (ref "U$1") (pin "8") (pinfunction "RP(I)121/RG9_8") (pintype "passive"))
    )
    (net (code "98") (name "unconnected-(U$1-RP65{slash}RD1-Pad49)") (class "Default")
      (node (ref "U$1") (pin "49") (pinfunction "RP65/RD1_49") (pintype "bidirectional"))
    )
    (net (code "99") (name "unconnected-(U$1-RP66{slash}RD2-Pad50)") (class "Default")
      (node (ref "U$1") (pin "50") (pinfunction "RP66/RD2_50") (pintype "bidirectional"))
    )
    (net (code "100") (name "unconnected-(U$1-RP67{slash}RD3-Pad51)") (class "Default")
      (node (ref "U$1") (pin "51") (pinfunction "RP67/RD3_51") (pintype "bidirectional"))
    )
    (net (code "101") (name "unconnected-(U$1-RP98{slash}RF2-Pad34)") (class "Default")
      (node (ref "U$1") (pin "34") (pinfunction "RP98/RF2_34") (pintype "bidirectional"))
    )
    (net (code "102") (name "unconnected-(U$1-RP102{slash}RF6-Pad35)") (class "Default")
      (node (ref "U$1") (pin "35") (pinfunction "RP102/RF6_35") (pintype "bidirectional"))
    )
  )
)
